# digital_input_protection.net
KiCad netlist of a schematic drawn in Altium Designer
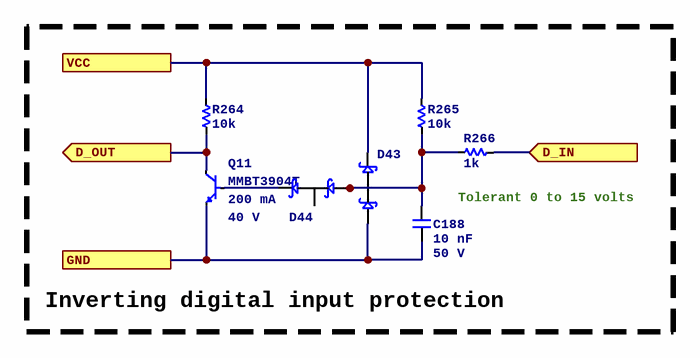
[diagram p0: digital_input_protection.SchDoc]

(export (version "E")
  (design (tool "Eeschema 10.0.6"))
  (components
    (comp (ref "C188")
      (value "CL05B103KB5NNNC")
      (footprint "C0402")
      (fields
        (field (name "CAPACITANCE") "10 nF")
        (field (name "MANUFACTURER") "Samsung Electro-Mechanics")
        (field (name "VOLTAGE RATING") "50 V")
      )
      (libsource (lib "database") (part "__template_cap"))
    )
    (comp (ref "D43")
      (value "BAT54SLT1G")
      (footprint "3SOT23")
      (description "DIODE SCHOTTKY DUAL 30V SOT23")
      (fields (field (name "MANUFACTURER") "ON Semiconductor"))
      (libsource (lib "database") (part "BAT54SLT1G"))
    )
    (comp (ref "D44")
      (value "BAT54SLT1G")
      (footprint "3SOT23")
      (description "DIODE SCHOTTKY DUAL 30V SOT23")
      (fields (field (name "MANUFACTURER") "ON Semiconductor"))
      (libsource (lib "database") (part "BAT54SLT1G"))
    )
    (comp (ref "Q11")
      (value "MMBT3904T")
      (footprint "3SOT523")
      (description "Bipolar (BJT) Transistor NPN 40 V 200 mA 300MHz 150 mW Surface Mount SOT-523")
      (fields
        (field (name "MANUFACTURER") "Shenzhen Slkormicro Semicon Co., Ltd.")
        (field (name "CURRENT") "200 mA")
        (field (name "VOLTAGE") "40 V")
      )
      (libsource (lib "database") (part "MMBT3904T"))
    )
    (comp (ref "R264")
      (value "10k")
      (footprint "R0402")
      (fields
        (field (name "TOLERANCE") "1%")
        (field (name "MANUFACTURER PART NUMBER") "0402WGF1002TCE")
        (field (name "MANUFACTURER") "UNI-ROYAL(Uniroyal Elec)")
      )
      (libsource (lib "database") (part "__template_resistor"))
    )
    (comp (ref "R265")
      (value "10k")
      (footprint "R0402")
      (fields
        (field (name "TOLERANCE") "1%")
        (field (name "MANUFACTURER PART NUMBER") "0402WGF1002TCE")
        (field (name "MANUFACTURER") "UNI-ROYAL(Uniroyal Elec)")
      )
      (libsource (lib "database") (part "__template_resistor"))
    )
    (comp (ref "R266")
      (value "1k")
      (footprint "R0805")
      (fields
        (field (name "TOLERANCE") "1%")
        (field (name "MANUFACTURER PART NUMBER") "HP05W3F1001T5E")
        (field (name "MANUFACTURER") "UNI-ROYAL(Uniroyal Elec)")
      )
      (libsource (lib "database") (part "__template_resistor"))
    )
  )
  (nets
    (net (code "1") (name "/D_IN") (class "Default") (node (ref "R266") (pin "1") (pintype "passive")))
    (net (code "2") (name "/D_OUT") (class "Default")
      (node (ref "Q11") (pin "3") (pinfunction "C_3") (pintype "passive"))
      (node (ref "R264") (pin "1") (pintype "passive"))
    )
    (net (code "3") (name "/GND") (class "Default")
      (node (ref "C188") (pin "2") (pintype "passive"))
      (node (ref "D43") (pin "1") (pintype "passive"))
      (node (ref "Q11") (pin "2") (pinfunction "E_2") (pintype "passive"))
    )
    (net (code "4") (name "/VCC") (class "Default")
      (node (ref "D43") (pin "2") (pintype "passive"))
      (node (ref "R264") (pin "2") (pintype "passive"))
      (node (ref "R265") (pin "2") (pintype "passive"))
    )
    (net (code "5") (name "Net-(C188-Pad1)") (class "Default")
      (node (ref "C188") (pin "1") (pintype "passive"))
      (node (ref "D43") (pin "3") (pintype "passive"))
      (node (ref "D44") (pin "1") (pintype "passive"))
      (node (ref "R265") (pin "1") (pintype "passive"))
      (node (ref "R266") (pin "2") (pintype "passive"))
    )
    (net (code "6") (name "Net-(Q11-B)") (class "Default")
      (node (ref "D44") (pin "2") (pintype "passive"))
      (node (ref "Q11") (pin "1") (pinfunction "B_1") (pintype "passive"))
    )
    (net (code "7") (name "unconnected-(D44-Pad3)") (class "Default")
      (node (ref "D44") (pin "3") (pintype "passive"))
    )
  )
)
